# Wio_-_Expansion_Board_RevB.net
KiCad netlist of a schematic drawn in EAGLE
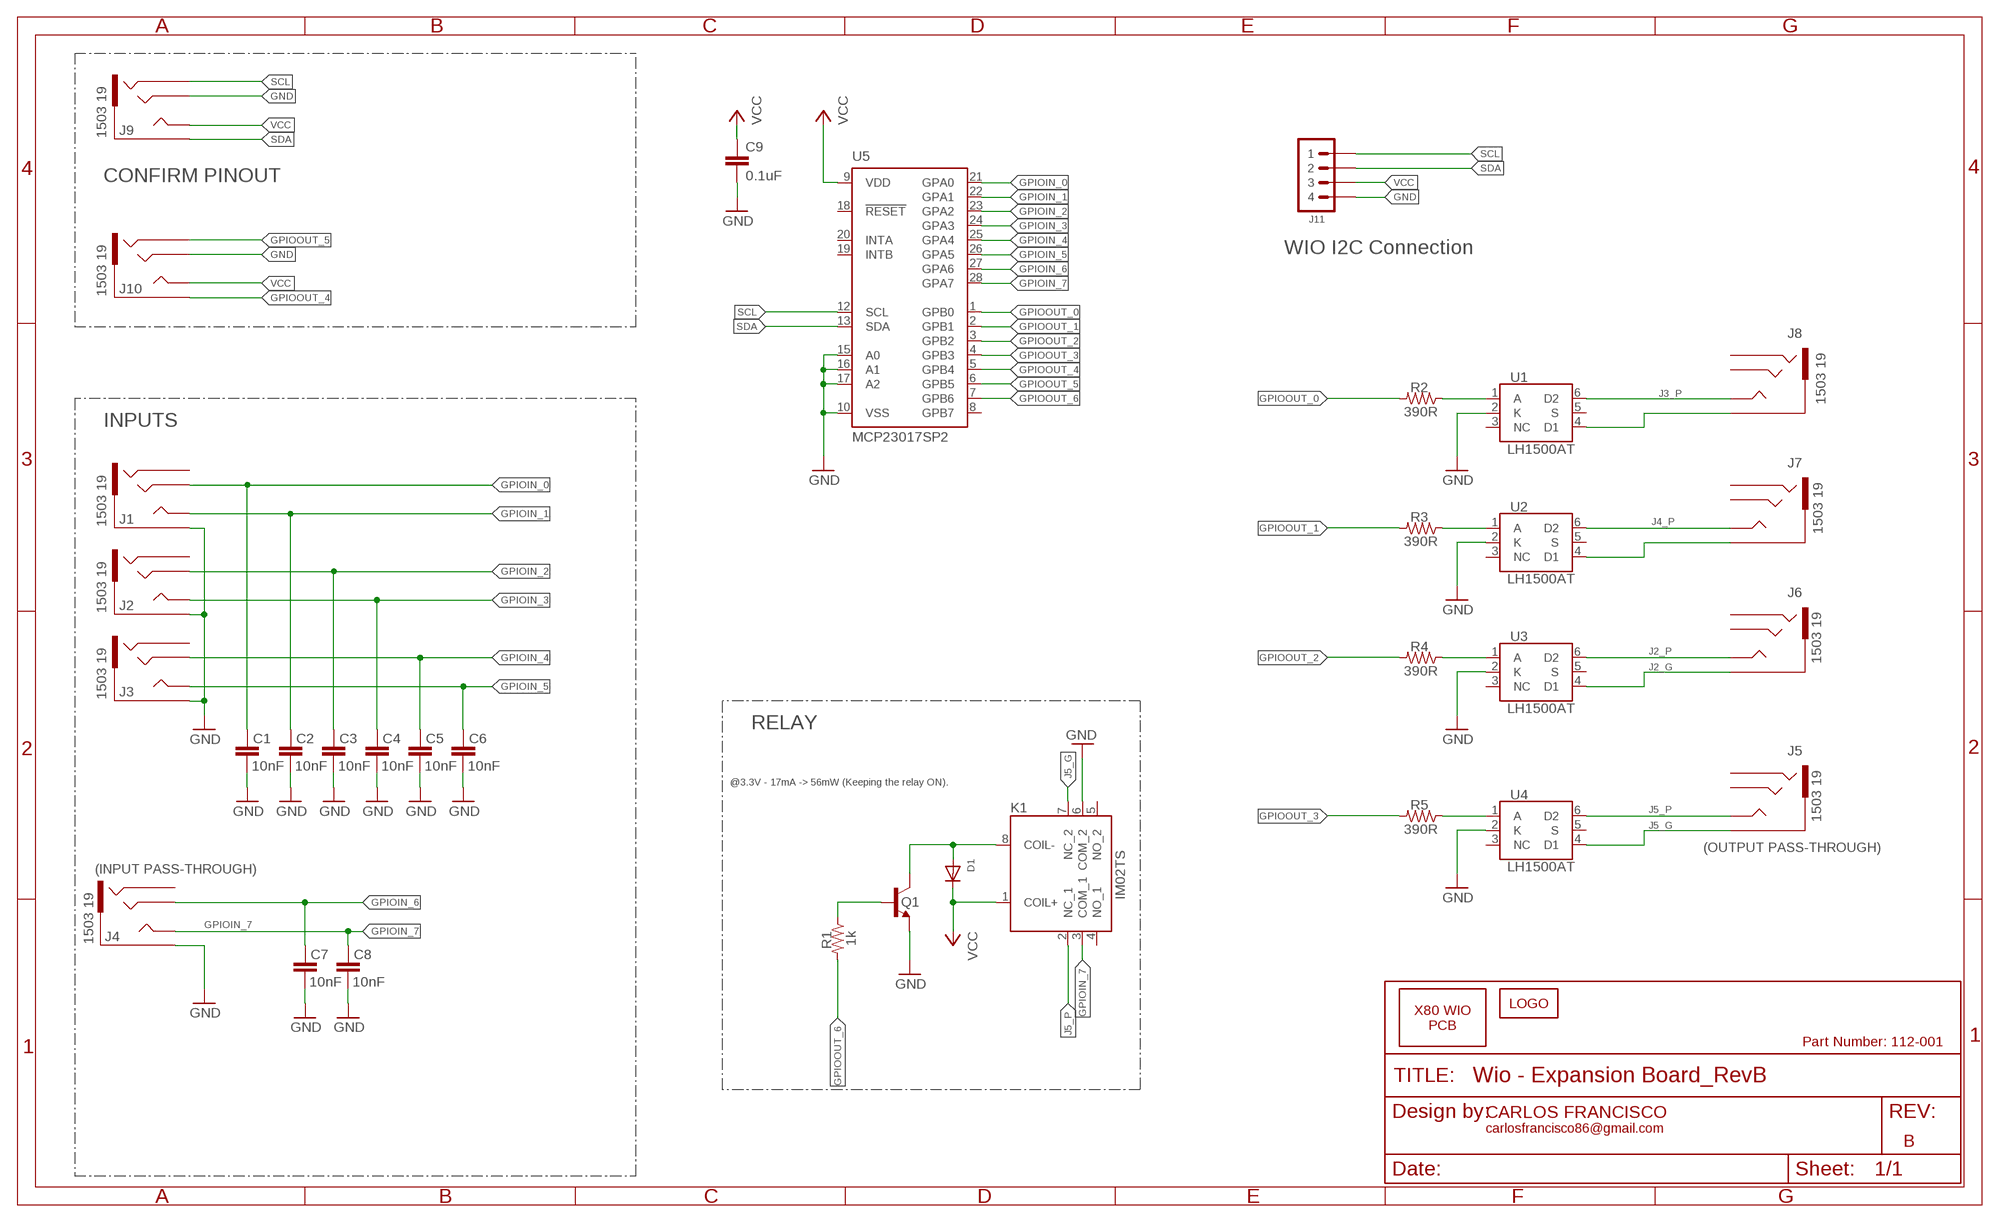
[diagram p0: schematic, sheet 1]

(export (version "E")
  (design (tool "Eeschema 10.0.6"))
  (components
    (comp (ref "C1")
      (value "10nF")
      (footprint "eagle-import:C025-024X044")
      (libsource (lib "eagle-import") (part "C-2.5P-2.4X4.4"))
    )
    (comp (ref "C2")
      (value "10nF")
      (footprint "eagle-import:C025-024X044")
      (libsource (lib "eagle-import") (part "C-2.5P-2.4X4.4"))
    )
    (comp (ref "C3")
      (value "10nF")
      (footprint "eagle-import:C025-024X044")
      (libsource (lib "eagle-import") (part "C-2.5P-2.4X4.4"))
    )
    (comp (ref "C4")
      (value "10nF")
      (footprint "eagle-import:C025-024X044")
      (libsource (lib "eagle-import") (part "C-2.5P-2.4X4.4"))
    )
    (comp (ref "C5")
      (value "10nF")
      (footprint "eagle-import:C025-024X044")
      (libsource (lib "eagle-import") (part "C-2.5P-2.4X4.4"))
    )
    (comp (ref "C6")
      (value "10nF")
      (footprint "eagle-import:C025-024X044")
      (libsource (lib "eagle-import") (part "C-2.5P-2.4X4.4"))
    )
    (comp (ref "C7")
      (value "10nF")
      (footprint "eagle-import:C025-024X044")
      (libsource (lib "eagle-import") (part "C-2.5P-2.4X4.4"))
    )
    (comp (ref "C8")
      (value "10nF")
      (footprint "eagle-import:C025-024X044")
      (libsource (lib "eagle-import") (part "C-2.5P-2.4X4.4"))
    )
    (comp (ref "C9")
      (value "0.1uF")
      (footprint "eagle-import:C025-025X050")
      (libsource (lib "eagle-import") (part "C-EU025-025X050"))
    )
    (comp (ref "D1")
      (value "1N4148")
      (footprint "eagle-import:DO-1N4148")
      (fields (field (name "MFR") "ON Semiconductor"))
      (libsource (lib "eagle-import") (part "DIODE-DO-35"))
    )
    (comp (ref "J1")
      (value "1503 19")
      (footprint "eagle-import:1503-19")
      (fields (field (name "MFR") "Lumberg"))
      (libsource (lib "eagle-import") (part "STEREO_JACK-1503-19"))
    )
    (comp (ref "J2")
      (value "1503 19")
      (footprint "eagle-import:1503-19")
      (fields (field (name "MFR") "Lumberg"))
      (libsource (lib "eagle-import") (part "STEREO_JACK-1503-19"))
    )
    (comp (ref "J3")
      (value "1503 19")
      (footprint "eagle-import:1503-19")
      (fields (field (name "MFR") "Lumberg"))
      (libsource (lib "eagle-import") (part "STEREO_JACK-1503-19"))
    )
    (comp (ref "J4")
      (value "1503 19")
      (footprint "eagle-import:1503-19")
      (fields (field (name "MFR") "Lumberg"))
      (libsource (lib "eagle-import") (part "STEREO_JACK-1503-19"))
    )
    (comp (ref "J5")
      (value "1503 19")
      (footprint "eagle-import:1503-19")
      (fields (field (name "MFR") "Lumberg"))
      (libsource (lib "eagle-import") (part "STEREO_JACK-1503-19"))
    )
    (comp (ref "J6")
      (value "1503 19")
      (footprint "eagle-import:1503-19")
      (fields (field (name "MFR") "Lumberg"))
      (libsource (lib "eagle-import") (part "STEREO_JACK-1503-19"))
    )
    (comp (ref "J7")
      (value "1503 19")
      (footprint "eagle-import:1503-19")
      (fields (field (name "MFR") "Lumberg"))
      (libsource (lib "eagle-import") (part "STEREO_JACK-1503-19"))
    )
    (comp (ref "J8")
      (value "1503 19")
      (footprint "eagle-import:1503-19")
      (fields (field (name "MFR") "Lumberg"))
      (libsource (lib "eagle-import") (part "STEREO_JACK-1503-19"))
    )
    (comp (ref "J9")
      (value "1503 19")
      (footprint "eagle-import:1503-19")
      (fields (field (name "MFR") "Lumberg"))
      (libsource (lib "eagle-import") (part "STEREO_JACK-1503-19"))
    )
    (comp (ref "J10")
      (value "1503 19")
      (footprint "eagle-import:1503-19")
      (fields (field (name "MFR") "Lumberg"))
      (libsource (lib "eagle-import") (part "STEREO_JACK-1503-19"))
    )
    (comp (ref "J11")
      (value "4P-2.0-90D")
      (footprint "eagle-import:HW4-2.0-90D")
      (libsource (lib "eagle-import") (part "CONN_04-GROOVE-RA-THT"))
    )
    (comp (ref "K1")
      (value "IM02TS")
      (footprint "eagle-import:IM03TS114620378")
      (fields (field (name "MFR") "TE Connectivity"))
      (libsource (lib "eagle-import") (part "IM02TS"))
    )
    (comp (ref "LOGO1")
      (value "LOGO-10MM")
      (footprint "eagle-import:LOGO_10MM")
      (libsource (lib "eagle-import") (part "LOGO-10MM"))
    )
    (comp (ref "PCB2")
      (value "X80_WIO_PCB-WIO_PCB_V1")
      (footprint "eagle-import:WIO_PCB")
      (libsource (lib "eagle-import") (part "X80_WIO_PCB-WIO_PCB_V1"))
    )
    (comp (ref "Q1")
      (value "PN2222A")
      (footprint "eagle-import:TO92-EBC-OVAL")
      (fields (field (name "MFR") "ON Semiconductor"))
      (libsource (lib "eagle-import") (part "NPN-TO-92"))
    )
    (comp (ref "R1")
      (value "1k")
      (footprint "eagle-import:0204_7")
      (libsource (lib "eagle-import") (part "R-0206-THT-RS"))
    )
    (comp (ref "R2")
      (value "390R")
      (footprint "eagle-import:0204_7")
      (libsource (lib "eagle-import") (part "R-0206-THT-RS"))
    )
    (comp (ref "R3")
      (value "390R")
      (footprint "eagle-import:0204_7")
      (libsource (lib "eagle-import") (part "R-0206-THT-RS"))
    )
    (comp (ref "R4")
      (value "390R")
      (footprint "eagle-import:0204_7")
      (libsource (lib "eagle-import") (part "R-0206-THT-RS"))
    )
    (comp (ref "R5")
      (value "390R")
      (footprint "eagle-import:0204_7")
      (libsource (lib "eagle-import") (part "R-0206-THT-RS"))
    )
    (comp (ref "U1")
      (value "LH1500AT")
      (footprint "eagle-import:DIP762W47P254L880H410Q6N")
      (fields (field (name "MFR") "Vishay"))
      (libsource (lib "eagle-import") (part "SSR-LH1500AT"))
    )
    (comp (ref "U2")
      (value "LH1500AT")
      (footprint "eagle-import:DIP762W47P254L880H410Q6N")
      (fields (field (name "MFR") "Vishay"))
      (libsource (lib "eagle-import") (part "SSR-LH1500AT"))
    )
    (comp (ref "U3")
      (value "LH1500AT")
      (footprint "eagle-import:DIP762W47P254L880H410Q6N")
      (fields (field (name "MFR") "Vishay"))
      (libsource (lib "eagle-import") (part "SSR-LH1500AT"))
    )
    (comp (ref "U4")
      (value "LH1500AT")
      (footprint "eagle-import:DIP762W47P254L880H410Q6N")
      (fields (field (name "MFR") "Vishay"))
      (libsource (lib "eagle-import") (part "SSR-LH1500AT"))
    )
    (comp (ref "U5")
      (value "MCP23017SP2")
      (footprint "eagle-import:DIL28-3-ROUND")
      (libsource (lib "eagle-import") (part "MCP23017SP2"))
    )
  )
  (nets
    (net (code "1") (name "/J2_G") (class "Default")
      (node (ref "J6") (pin "1") (pinfunction "1_1") (pintype "bidirectional"))
      (node (ref "U3") (pin "4") (pinfunction "D1_4") (pintype "bidirectional"))
    )
    (net (code "2") (name "/J2_P") (class "Default")
      (node (ref "J6") (pin "4") (pinfunction "4_4") (pintype "bidirectional"))
      (node (ref "J6") (pin "5") (pinfunction "4_5") (pintype "bidirectional"))
      (node (ref "U3") (pin "6") (pinfunction "D2_6") (pintype "bidirectional"))
    )
    (net (code "3") (name "/J3_P") (class "Default")
      (node (ref "J8") (pin "4") (pinfunction "4_4") (pintype "bidirectional"))
      (node (ref "J8") (pin "5") (pinfunction "4_5") (pintype "bidirectional"))
      (node (ref "U1") (pin "6") (pinfunction "D2_6") (pintype "bidirectional"))
    )
    (net (code "4") (name "/J4_P") (class "Default")
      (node (ref "J7") (pin "4") (pinfunction "4_4") (pintype "bidirectional"))
      (node (ref "J7") (pin "5") (pinfunction "4_5") (pintype "bidirectional"))
      (node (ref "U2") (pin "6") (pinfunction "D2_6") (pintype "bidirectional"))
    )
    (net (code "5") (name "GND") (class "Default")
      (node (ref "C1") (pin "2") (pinfunction "2_2") (pintype "passive"))
      (node (ref "C2") (pin "2") (pinfunction "2_2") (pintype "passive"))
      (node (ref "C3") (pin "2") (pinfunction "2_2") (pintype "passive"))
      (node (ref "C4") (pin "2") (pinfunction "2_2") (pintype "passive"))
      (node (ref "C5") (pin "2") (pinfunction "2_2") (pintype "passive"))
      (node (ref "C6") (pin "2") (pinfunction "2_2") (pintype "passive"))
      (node (ref "C7") (pin "2") (pinfunction "2_2") (pintype "passive"))
      (node (ref "C8") (pin "2") (pinfunction "2_2") (pintype "passive"))
      (node (ref "C9") (pin "2") (pinfunction "2_2") (pintype "passive"))
      (node (ref "J1") (pin "1") (pinfunction "1_1") (pintype "bidirectional"))
      (node (ref "J10") (pin "3") (pinfunction "3_3") (pintype "bidirectional"))
      (node (ref "J11") (pin "4") (pinfunction "4_4") (pintype "passive"))
      (node (ref "J2") (pin "1") (pinfunction "1_1") (pintype "bidirectional"))
      (node (ref "J3") (pin "1") (pinfunction "1_1") (pintype "bidirectional"))
      (node (ref "J4") (pin "1") (pinfunction "1_1") (pintype "bidirectional"))
      (node (ref "J9") (pin "3") (pinfunction "3_3") (pintype "bidirectional"))
      (node (ref "K1") (pin "6") (pinfunction "COM_2_6") (pintype "bidirectional"))
      (node (ref "Q1") (pin "E") (pinfunction "E_E") (pintype "passive"))
      (node (ref "U1") (pin "2") (pinfunction "K_2") (pintype "bidirectional"))
      (node (ref "U2") (pin "2") (pinfunction "K_2") (pintype "bidirectional"))
      (node (ref "U3") (pin "2") (pinfunction "K_2") (pintype "bidirectional"))
      (node (ref "U4") (pin "2") (pinfunction "K_2") (pintype "bidirectional"))
      (node (ref "U5") (pin "10") (pinfunction "VSS_10") (pintype "power_in"))
      (node (ref "U5") (pin "15") (pinfunction "A0_15") (pintype "input"))
      (node (ref "U5") (pin "16") (pinfunction "A1_16") (pintype "input"))
      (node (ref "U5") (pin "17") (pinfunction "A2_17") (pintype "input"))
    )
    (net (code "6") (name "GPIOIN_0") (class "Default")
      (node (ref "C1") (pin "1") (pinfunction "1_1") (pintype "passive"))
      (node (ref "J1") (pin "3") (pinfunction "3_3") (pintype "bidirectional"))
      (node (ref "U5") (pin "21") (pinfunction "GPA0_21") (pintype "bidirectional"))
    )
    (net (code "7") (name "GPIOIN_1") (class "Default")
      (node (ref "C2") (pin "1") (pinfunction "1_1") (pintype "passive"))
      (node (ref "J1") (pin "4") (pinfunction "4_4") (pintype "bidirectional"))
      (node (ref "J1") (pin "5") (pinfunction "4_5") (pintype "bidirectional"))
      (node (ref "U5") (pin "22") (pinfunction "GPA1_22") (pintype "bidirectional"))
    )
    (net (code "8") (name "GPIOIN_2") (class "Default")
      (node (ref "C3") (pin "1") (pinfunction "1_1") (pintype "passive"))
      (node (ref "J2") (pin "3") (pinfunction "3_3") (pintype "bidirectional"))
      (node (ref "U5") (pin "23") (pinfunction "GPA2_23") (pintype "bidirectional"))
    )
    (net (code "9") (name "GPIOIN_3") (class "Default")
      (node (ref "C4") (pin "1") (pinfunction "1_1") (pintype "passive"))
      (node (ref "J2") (pin "4") (pinfunction "4_4") (pintype "bidirectional"))
      (node (ref "J2") (pin "5") (pinfunction "4_5") (pintype "bidirectional"))
      (node (ref "U5") (pin "24") (pinfunction "GPA3_24") (pintype "bidirectional"))
    )
    (net (code "10") (name "GPIOIN_4") (class "Default")
      (node (ref "C5") (pin "1") (pinfunction "1_1") (pintype "passive"))
      (node (ref "J3") (pin "3") (pinfunction "3_3") (pintype "bidirectional"))
      (node (ref "U5") (pin "25") (pinfunction "GPA4_25") (pintype "bidirectional"))
    )
    (net (code "11") (name "GPIOIN_5") (class "Default")
      (node (ref "C6") (pin "1") (pinfunction "1_1") (pintype "passive"))
      (node (ref "J3") (pin "4") (pinfunction "4_4") (pintype "bidirectional"))
      (node (ref "J3") (pin "5") (pinfunction "4_5") (pintype "bidirectional"))
      (node (ref "U5") (pin "26") (pinfunction "GPA5_26") (pintype "bidirectional"))
    )
    (net (code "12") (name "GPIOIN_6") (class "Default")
      (node (ref "C7") (pin "1") (pinfunction "1_1") (pintype "passive"))
      (node (ref "J4") (pin "3") (pinfunction "3_3") (pintype "bidirectional"))
      (node (ref "U5") (pin "27") (pinfunction "GPA6_27") (pintype "bidirectional"))
    )
    (net (code "13") (name "GPIOIN_7") (class "Default")
      (node (ref "C8") (pin "1") (pinfunction "1_1") (pintype "passive"))
      (node (ref "J4") (pin "4") (pinfunction "4_4") (pintype "bidirectional"))
      (node (ref "J4") (pin "5") (pinfunction "4_5") (pintype "bidirectional"))
      (node (ref "K1") (pin "3") (pinfunction "COM_1_3") (pintype "bidirectional"))
      (node (ref "U5") (pin "28") (pinfunction "GPA7_28") (pintype "bidirectional"))
    )
    (net (code "14") (name "GPIOOUT_0") (class "Default")
      (node (ref "R2") (pin "1") (pinfunction "1_1") (pintype "passive"))
      (node (ref "U5") (pin "1") (pinfunction "GPB0_1") (pintype "bidirectional"))
    )
    (net (code "15") (name "GPIOOUT_1") (class "Default")
      (node (ref "R3") (pin "1") (pinfunction "1_1") (pintype "passive"))
      (node (ref "U5") (pin "2") (pinfunction "GPB1_2") (pintype "bidirectional"))
    )
    (net (code "16") (name "GPIOOUT_2") (class "Default")
      (node (ref "R4") (pin "1") (pinfunction "1_1") (pintype "passive"))
      (node (ref "U5") (pin "3") (pinfunction "GPB2_3") (pintype "bidirectional"))
    )
    (net (code "17") (name "GPIOOUT_3") (class "Default")
      (node (ref "R5") (pin "1") (pinfunction "1_1") (pintype "passive"))
      (node (ref "U5") (pin "4") (pinfunction "GPB3_4") (pintype "bidirectional"))
    )
    (net (code "18") (name "GPIOOUT_4") (class "Default")
      (node (ref "J10") (pin "1") (pinfunction "1_1") (pintype "bidirectional"))
      (node (ref "U5") (pin "5") (pinfunction "GPB4_5") (pintype "bidirectional"))
    )
    (net (code "19") (name "GPIOOUT_5") (class "Default")
      (node (ref "J10") (pin "2") (pinfunction "2_2") (pintype "bidirectional"))
      (node (ref "U5") (pin "6") (pinfunction "GPB5_6") (pintype "bidirectional"))
    )
    (net (code "20") (name "GPIOOUT_6") (class "Default")
      (node (ref "R1") (pin "1") (pinfunction "1_1") (pintype "passive"))
      (node (ref "U5") (pin "7") (pinfunction "GPB6_7") (pintype "bidirectional"))
    )
    (net (code "21") (name "J5_G") (class "Default")
      (node (ref "J5") (pin "1") (pinfunction "1_1") (pintype "bidirectional"))
      (node (ref "K1") (pin "7") (pinfunction "NC_2_7") (pintype "bidirectional"))
      (node (ref "U4") (pin "4") (pinfunction "D1_4") (pintype "bidirectional"))
    )
    (net (code "22") (name "J5_P") (class "Default")
      (node (ref "J5") (pin "4") (pinfunction "4_4") (pintype "bidirectional"))
      (node (ref "J5") (pin "5") (pinfunction "4_5") (pintype "bidirectional"))
      (node (ref "K1") (pin "2") (pinfunction "NC_1_2") (pintype "bidirectional"))
      (node (ref "U4") (pin "6") (pinfunction "D2_6") (pintype "bidirectional"))
    )
    (net (code "23") (name "Net-(K1-COIL-)") (class "Default")
      (node (ref "D1") (pin "A") (pinfunction "A_A") (pintype "passive"))
      (node (ref "K1") (pin "8") (pinfunction "COIL-_8") (pintype "bidirectional"))
      (node (ref "Q1") (pin "C") (pinfunction "C_C") (pintype "passive"))
    )
    (net (code "24") (name "Net-(Q1-PadB)") (class "Default")
      (node (ref "Q1") (pin "B") (pinfunction "B_B") (pintype "passive"))
      (node (ref "R1") (pin "2") (pinfunction "2_2") (pintype "passive"))
    )
    (net (code "25") (name "Net-(U1-A)") (class "Default")
      (node (ref "R2") (pin "2") (pinfunction "2_2") (pintype "passive"))
      (node (ref "U1") (pin "1") (pinfunction "A_1") (pintype "bidirectional"))
    )
    (net (code "26") (name "Net-(U1-D1)") (class "Default")
      (node (ref "J8") (pin "1") (pinfunction "1_1") (pintype "bidirectional"))
      (node (ref "U1") (pin "4") (pinfunction "D1_4") (pintype "bidirectional"))
    )
    (net (code "27") (name "Net-(U2-A)") (class "Default")
      (node (ref "R3") (pin "2") (pinfunction "2_2") (pintype "passive"))
      (node (ref "U2") (pin "1") (pinfunction "A_1") (pintype "bidirectional"))
    )
    (net (code "28") (name "Net-(U2-D1)") (class "Default")
      (node (ref "J7") (pin "1") (pinfunction "1_1") (pintype "bidirectional"))
      (node (ref "U2") (pin "4") (pinfunction "D1_4") (pintype "bidirectional"))
    )
    (net (code "29") (name "Net-(U3-A)") (class "Default")
      (node (ref "R4") (pin "2") (pinfunction "2_2") (pintype "passive"))
      (node (ref "U3") (pin "1") (pinfunction "A_1") (pintype "bidirectional"))
    )
    (net (code "30") (name "Net-(U4-A)") (class "Default")
      (node (ref "R5") (pin "2") (pinfunction "2_2") (pintype "passive"))
      (node (ref "U4") (pin "1") (pinfunction "A_1") (pintype "bidirectional"))
    )
    (net (code "31") (name "SCL") (class "Default")
      (node (ref "J11") (pin "1") (pinfunction "1_1") (pintype "passive"))
      (node (ref "J9") (pin "2") (pinfunction "2_2") (pintype "bidirectional"))
      (node (ref "U5") (pin "12") (pinfunction "SCL_12") (pintype "input"))
    )
    (net (code "32") (name "SDA") (class "Default")
      (node (ref "J11") (pin "2") (pinfunction "2_2") (pintype "passive"))
      (node (ref "J9") (pin "1") (pinfunction "1_1") (pintype "bidirectional"))
      (node (ref "U5") (pin "13") (pinfunction "SDA_13") (pintype "bidirectional"))
    )
    (net (code "33") (name "VCC") (class "Default")
      (node (ref "C9") (pin "1") (pinfunction "1_1") (pintype "passive"))
      (node (ref "D1") (pin "C") (pinfunction "C_C") (pintype "passive"))
      (node (ref "J10") (pin "4") (pinfunction "4_4") (pintype "bidirectional"))
      (node (ref "J10") (pin "5") (pinfunction "4_5") (pintype "bidirectional"))
      (node (ref "J11") (pin "3") (pinfunction "3_3") (pintype "passive"))
      (node (ref "J9") (pin "4") (pinfunction "4_4") (pintype "bidirectional"))
      (node (ref "J9") (pin "5") (pinfunction "4_5") (pintype "bidirectional"))
      (node (ref "K1") (pin "1") (pinfunction "COIL+_1") (pintype "bidirectional"))
      (node (ref "U5") (pin "9") (pinfunction "VDD_9") (pintype "power_in"))
    )
    (net (code "34") (name "unconnected-(J1-Pad2)") (class "Default")
      (node (ref "J1") (pin "2") (pinfunction "2_2") (pintype "bidirectional"))
    )
    (net (code "35") (name "unconnected-(J2-Pad2)") (class "Default")
      (node (ref "J2") (pin "2") (pinfunction "2_2") (pintype "bidirectional"))
    )
    (net (code "36") (name "unconnected-(J3-Pad2)") (class "Default")
      (node (ref "J3") (pin "2") (pinfunction "2_2") (pintype "bidirectional"))
    )
    (net (code "37") (name "unconnected-(J4-Pad2)") (class "Default")
      (node (ref "J4") (pin "2") (pinfunction "2_2") (pintype "bidirectional"))
    )
    (net (code "38") (name "unconnected-(J5-Pad2)") (class "Default")
      (node (ref "J5") (pin "2") (pinfunction "2_2") (pintype "bidirectional"))
    )
    (net (code "39") (name "unconnected-(J5-Pad3)") (class "Default")
      (node (ref "J5") (pin "3") (pinfunction "3_3") (pintype "bidirectional"))
    )
    (net (code "40") (name "unconnected-(J6-Pad2)") (class "Default")
      (node (ref "J6") (pin "2") (pinfunction "2_2") (pintype "bidirectional"))
    )
    (net (code "41") (name "unconnected-(J6-Pad3)") (class "Default")
      (node (ref "J6") (pin "3") (pinfunction "3_3") (pintype "bidirectional"))
    )
    (net (code "42") (name "unconnected-(J7-Pad2)") (class "Default")
      (node (ref "J7") (pin "2") (pinfunction "2_2") (pintype "bidirectional"))
    )
    (net (code "43") (name "unconnected-(J7-Pad3)") (class "Default")
      (node (ref "J7") (pin "3") (pinfunction "3_3") (pintype "bidirectional"))
    )
    (net (code "44") (name "unconnected-(J8-Pad2)") (class "Default")
      (node (ref "J8") (pin "2") (pinfunction "2_2") (pintype "bidirectional"))
    )
    (net (code "45") (name "unconnected-(J8-Pad3)") (class "Default")
      (node (ref "J8") (pin "3") (pinfunction "3_3") (pintype "bidirectional"))
    )
    (net (code "46") (name "unconnected-(K1-NO_1-Pad4)") (class "Default")
      (node (ref "K1") (pin "4") (pinfunction "NO_1_4") (pintype "bidirectional"))
    )
    (net (code "47") (name "unconnected-(K1-NO_2-Pad5)") (class "Default")
      (node (ref "K1") (pin "5") (pinfunction "NO_2_5") (pintype "bidirectional"))
    )
    (net (code "48") (name "unconnected-(U1-NC-Pad3)") (class "Default")
      (node (ref "U1") (pin "3") (pinfunction "NC_3") (pintype "no_connect"))
    )
    (net (code "49") (name "unconnected-(U1-S-Pad5)") (class "Default")
      (node (ref "U1") (pin "5") (pinfunction "S_5") (pintype "bidirectional"))
    )
    (net (code "50") (name "unconnected-(U2-NC-Pad3)") (class "Default")
      (node (ref "U2") (pin "3") (pinfunction "NC_3") (pintype "no_connect"))
    )
    (net (code "51") (name "unconnected-(U2-S-Pad5)") (class "Default")
      (node (ref "U2") (pin "5") (pinfunction "S_5") (pintype "bidirectional"))
    )
    (net (code "52") (name "unconnected-(U3-NC-Pad3)") (class "Default")
      (node (ref "U3") (pin "3") (pinfunction "NC_3") (pintype "no_connect"))
    )
    (net (code "53") (name "unconnected-(U3-S-Pad5)") (class "Default")
      (node (ref "U3") (pin "5") (pinfunction "S_5") (pintype "bidirectional"))
    )
    (net (code "54") (name "unconnected-(U4-NC-Pad3)") (class "Default")
      (node (ref "U4") (pin "3") (pinfunction "NC_3") (pintype "no_connect"))
    )
    (net (code "55") (name "unconnected-(U4-S-Pad5)") (class "Default")
      (node (ref "U4") (pin "5") (pinfunction "S_5") (pintype "bidirectional"))
    )
    (net (code "56") (name "unconnected-(U5-GPB7-Pad8)") (class "Default")
      (node (ref "U5") (pin "8") (pinfunction "GPB7_8") (pintype "bidirectional"))
    )
    (net (code "57") (name "unconnected-(U5-INTA-Pad20)") (class "Default")
      (node (ref "U5") (pin "20") (pinfunction "INTA_20") (pintype "output"))
    )
    (net (code "58") (name "unconnected-(U5-INTB-Pad19)") (class "Default")
      (node (ref "U5") (pin "19") (pinfunction "INTB_19") (pintype "output"))
    )
    (net (code "59") (name "unconnected-(U5-~{RESET}-Pad18)") (class "Default")
      (node (ref "U5") (pin "18") (pinfunction "~{RESET}_18") (pintype "input"))
    )
  )
)
